# schema_attiny85_Charger_NiMH.net
KiCad netlist of a schematic drawn in EAGLE
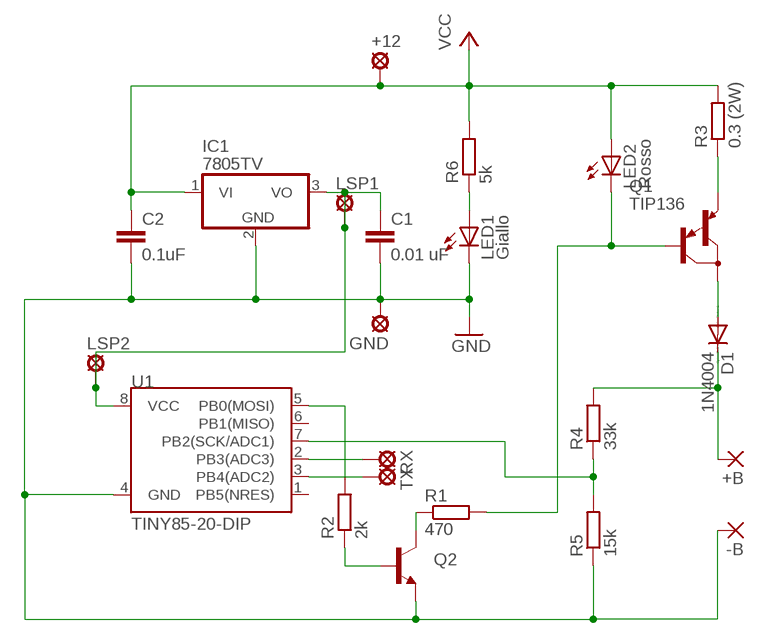
[diagram p0: schematic, sheet 1]

(export (version "E")
  (design (tool "Eeschema 10.0.6"))
  (components
    (comp (ref "+12")
      (value "LSP10")
      (footprint "eagle-import:LSP10")
      (libsource (lib "eagle-import") (part "LSP10"))
    )
    (comp (ref "+B")
      (value "1,6/0,9")
      (footprint "eagle-import:1,6_0,9")
      (libsource (lib "eagle-import") (part "1,6/0,9"))
    )
    (comp (ref "-B")
      (value "1,6/0,9")
      (footprint "eagle-import:1,6_0,9")
      (libsource (lib "eagle-import") (part "1,6/0,9"))
    )
    (comp (ref "C1")
      (value "0.01 uF")
      (footprint "eagle-import:C050-025X075")
      (libsource (lib "eagle-import") (part "C-EU050-025X075"))
    )
    (comp (ref "C2")
      (value "0.1uF")
      (footprint "eagle-import:C050-025X075")
      (libsource (lib "eagle-import") (part "C-EU050-025X075"))
    )
    (comp (ref "D1")
      (value "1N4004")
      (footprint "eagle-import:DO41-10")
      (libsource (lib "eagle-import") (part "1N4004"))
    )
    (comp (ref "GND")
      (value "LSP10")
      (footprint "eagle-import:LSP10")
      (libsource (lib "eagle-import") (part "LSP10"))
    )
    (comp (ref "IC1")
      (value "7805TV")
      (footprint "eagle-import:TO220V")
      (libsource (lib "eagle-import") (part "78TV05"))
    )
    (comp (ref "LED1")
      (value "Giallo")
      (footprint "eagle-import:LED5MM")
      (libsource (lib "eagle-import") (part "LED5MM"))
    )
    (comp (ref "LED2")
      (value "Rosso")
      (footprint "eagle-import:LED5MM")
      (libsource (lib "eagle-import") (part "LED5MM"))
    )
    (comp (ref "LSP1")
      (value "LSP10")
      (footprint "eagle-import:LSP10")
      (libsource (lib "eagle-import") (part "LSP10"))
    )
    (comp (ref "LSP2")
      (value "LSP10")
      (footprint "eagle-import:LSP10")
      (libsource (lib "eagle-import") (part "LSP10"))
    )
    (comp (ref "Q1")
      (value "TIP136")
      (footprint "eagle-import:TO220")
      (libsource (lib "eagle-import") (part "TIP136"))
    )
    (comp (ref "Q2")
      (value "TRANSISTOR_NPNBC547")
      (footprint "eagle-import:TO-92-AMMO")
      (libsource (lib "eagle-import") (part "TRANSISTOR_NPNBC547"))
    )
    (comp (ref "R1")
      (value "470")
      (footprint "eagle-import:0204_7")
      (libsource (lib "eagle-import") (part "R-EU_0204/7"))
    )
    (comp (ref "R2")
      (value "2k")
      (footprint "eagle-import:0204_7")
      (libsource (lib "eagle-import") (part "R-EU_0204/7"))
    )
    (comp (ref "R3")
      (value "0.3 (2W)")
      (footprint "eagle-import:0204_7")
      (libsource (lib "eagle-import") (part "R-EU_0204/7"))
    )
    (comp (ref "R4")
      (value "33k")
      (footprint "eagle-import:0204_7")
      (libsource (lib "eagle-import") (part "R-EU_0204/7"))
    )
    (comp (ref "R5")
      (value "15k")
      (footprint "eagle-import:0204_7")
      (libsource (lib "eagle-import") (part "R-EU_0204/7"))
    )
    (comp (ref "R6")
      (value "5k")
      (footprint "eagle-import:0204_7")
      (libsource (lib "eagle-import") (part "R-EU_0204/7"))
    )
    (comp (ref "RX")
      (value "LSP10")
      (footprint "eagle-import:LSP10")
      (libsource (lib "eagle-import") (part "LSP10"))
    )
    (comp (ref "TX")
      (value "LSP10")
      (footprint "eagle-import:LSP10")
      (libsource (lib "eagle-import") (part "LSP10"))
    )
    (comp (ref "U1")
      (value "TINY85-20-DIP")
      (footprint "eagle-import:DIP08")
      (libsource (lib "eagle-import") (part "ATTINY45TINY85-20-DIP"))
    )
  )
  (nets
    (net (code "1") (name "GND") (class "Default")
      (node (ref "-B") (pin "1") (pinfunction "P_1") (pintype "passive"))
      (node (ref "C1") (pin "2") (pinfunction "2_2") (pintype "passive"))
      (node (ref "C2") (pin "2") (pinfunction "2_2") (pintype "passive"))
      (node (ref "GND") (pin "MP") (pinfunction "MP_MP") (pintype "passive"))
      (node (ref "IC1") (pin "2") (pinfunction "GND_2") (pintype "passive"))
      (node (ref "LED1") (pin "K") (pinfunction "C_K") (pintype "passive"))
      (node (ref "Q2") (pin "3") (pinfunction "E_3") (pintype "passive"))
      (node (ref "R5") (pin "1") (pinfunction "1_1") (pintype "passive"))
      (node (ref "U1") (pin "4") (pinfunction "GND_4") (pintype "bidirectional"))
    )
    (net (code "2") (name "Net-(+B-P)") (class "Default")
      (node (ref "+B") (pin "1") (pinfunction "P_1") (pintype "passive"))
      (node (ref "D1") (pin "C") (pinfunction "C_C") (pintype "passive"))
      (node (ref "R4") (pin "2") (pinfunction "2_2") (pintype "passive"))
    )
    (net (code "3") (name "Net-(IC1-VO)") (class "Default")
      (node (ref "C1") (pin "1") (pinfunction "1_1") (pintype "passive"))
      (node (ref "IC1") (pin "3") (pinfunction "VO_3") (pintype "passive"))
      (node (ref "LSP1") (pin "MP") (pinfunction "MP_MP") (pintype "passive"))
      (node (ref "LSP2") (pin "MP") (pinfunction "MP_MP") (pintype "passive"))
      (node (ref "U1") (pin "8") (pinfunction "VCC_8") (pintype "bidirectional"))
    )
    (net (code "4") (name "Net-(LED1-PadA)") (class "Default")
      (node (ref "LED1") (pin "A") (pinfunction "A_A") (pintype "passive"))
      (node (ref "R6") (pin "1") (pinfunction "1_1") (pintype "passive"))
    )
    (net (code "5") (name "Net-(LED2-C)") (class "Default")
      (node (ref "LED2") (pin "K") (pinfunction "C_K") (pintype "passive"))
      (node (ref "Q1") (pin "1") (pinfunction "B_1") (pintype "passive"))
      (node (ref "R1") (pin "2") (pinfunction "2_2") (pintype "passive"))
    )
    (net (code "6") (name "Net-(Q1-C)") (class "Default")
      (node (ref "D1") (pin "A") (pinfunction "A_A") (pintype "passive"))
      (node (ref "Q1") (pin "2") (pinfunction "C_2") (pintype "passive"))
    )
    (net (code "7") (name "Net-(Q1-E)") (class "Default")
      (node (ref "Q1") (pin "3") (pinfunction "E_3") (pintype "passive"))
      (node (ref "R3") (pin "1") (pinfunction "1_1") (pintype "passive"))
    )
    (net (code "8") (name "Net-(Q2-B)") (class "Default")
      (node (ref "Q2") (pin "2") (pinfunction "B_2") (pintype "passive"))
      (node (ref "R2") (pin "1") (pinfunction "1_1") (pintype "passive"))
    )
    (net (code "9") (name "Net-(Q2-C)") (class "Default")
      (node (ref "Q2") (pin "1") (pinfunction "C_1") (pintype "passive"))
      (node (ref "R1") (pin "1") (pinfunction "1_1") (pintype "passive"))
    )
    (net (code "10") (name "Net-(U1-PB0(MOSI))") (class "Default")
      (node (ref "R2") (pin "2") (pinfunction "2_2") (pintype "passive"))
      (node (ref "U1") (pin "5") (pinfunction "PB0(MOSI)_5") (pintype "bidirectional"))
    )
    (net (code "11") (name "Net-(U1-PB2(SCK{slash}ADC1))") (class "Default")
      (node (ref "R4") (pin "1") (pinfunction "1_1") (pintype "passive"))
      (node (ref "R5") (pin "2") (pinfunction "2_2") (pintype "passive"))
      (node (ref "U1") (pin "7") (pinfunction "PB2(SCK/ADC1)_7") (pintype "bidirectional"))
    )
    (net (code "12") (name "Net-(U1-PB3(ADC3))") (class "Default")
      (node (ref "RX") (pin "MP") (pinfunction "MP_MP") (pintype "passive"))
      (node (ref "U1") (pin "2") (pinfunction "PB3(ADC3)_2") (pintype "bidirectional"))
    )
    (net (code "13") (name "Net-(U1-PB4(ADC2))") (class "Default")
      (node (ref "TX") (pin "MP") (pinfunction "MP_MP") (pintype "passive"))
      (node (ref "U1") (pin "3") (pinfunction "PB4(ADC2)_3") (pintype "bidirectional"))
    )
    (net (code "14") (name "VCC") (class "Default")
      (node (ref "+12") (pin "MP") (pinfunction "MP_MP") (pintype "passive"))
      (node (ref "C2") (pin "1") (pinfunction "1_1") (pintype "passive"))
      (node (ref "IC1") (pin "1") (pinfunction "VI_1") (pintype "input"))
      (node (ref "LED2") (pin "A") (pinfunction "A_A") (pintype "passive"))
      (node (ref "R3") (pin "2") (pinfunction "2_2") (pintype "passive"))
      (node (ref "R6") (pin "2") (pinfunction "2_2") (pintype "passive"))
    )
    (net (code "15") (name "unconnected-(U1-PB1(MISO)-Pad6)") (class "Default")
      (node (ref "U1") (pin "6") (pinfunction "PB1(MISO)_6") (pintype "bidirectional"))
    )
    (net (code "16") (name "unconnected-(U1-PB5(NRES)-Pad1)") (class "Default")
      (node (ref "U1") (pin "1") (pinfunction "PB5(NRES)_1") (pintype "bidirectional"))
    )
  )
)
